# ESP-01_daughter_board.net
KiCad netlist of a schematic drawn in EAGLE
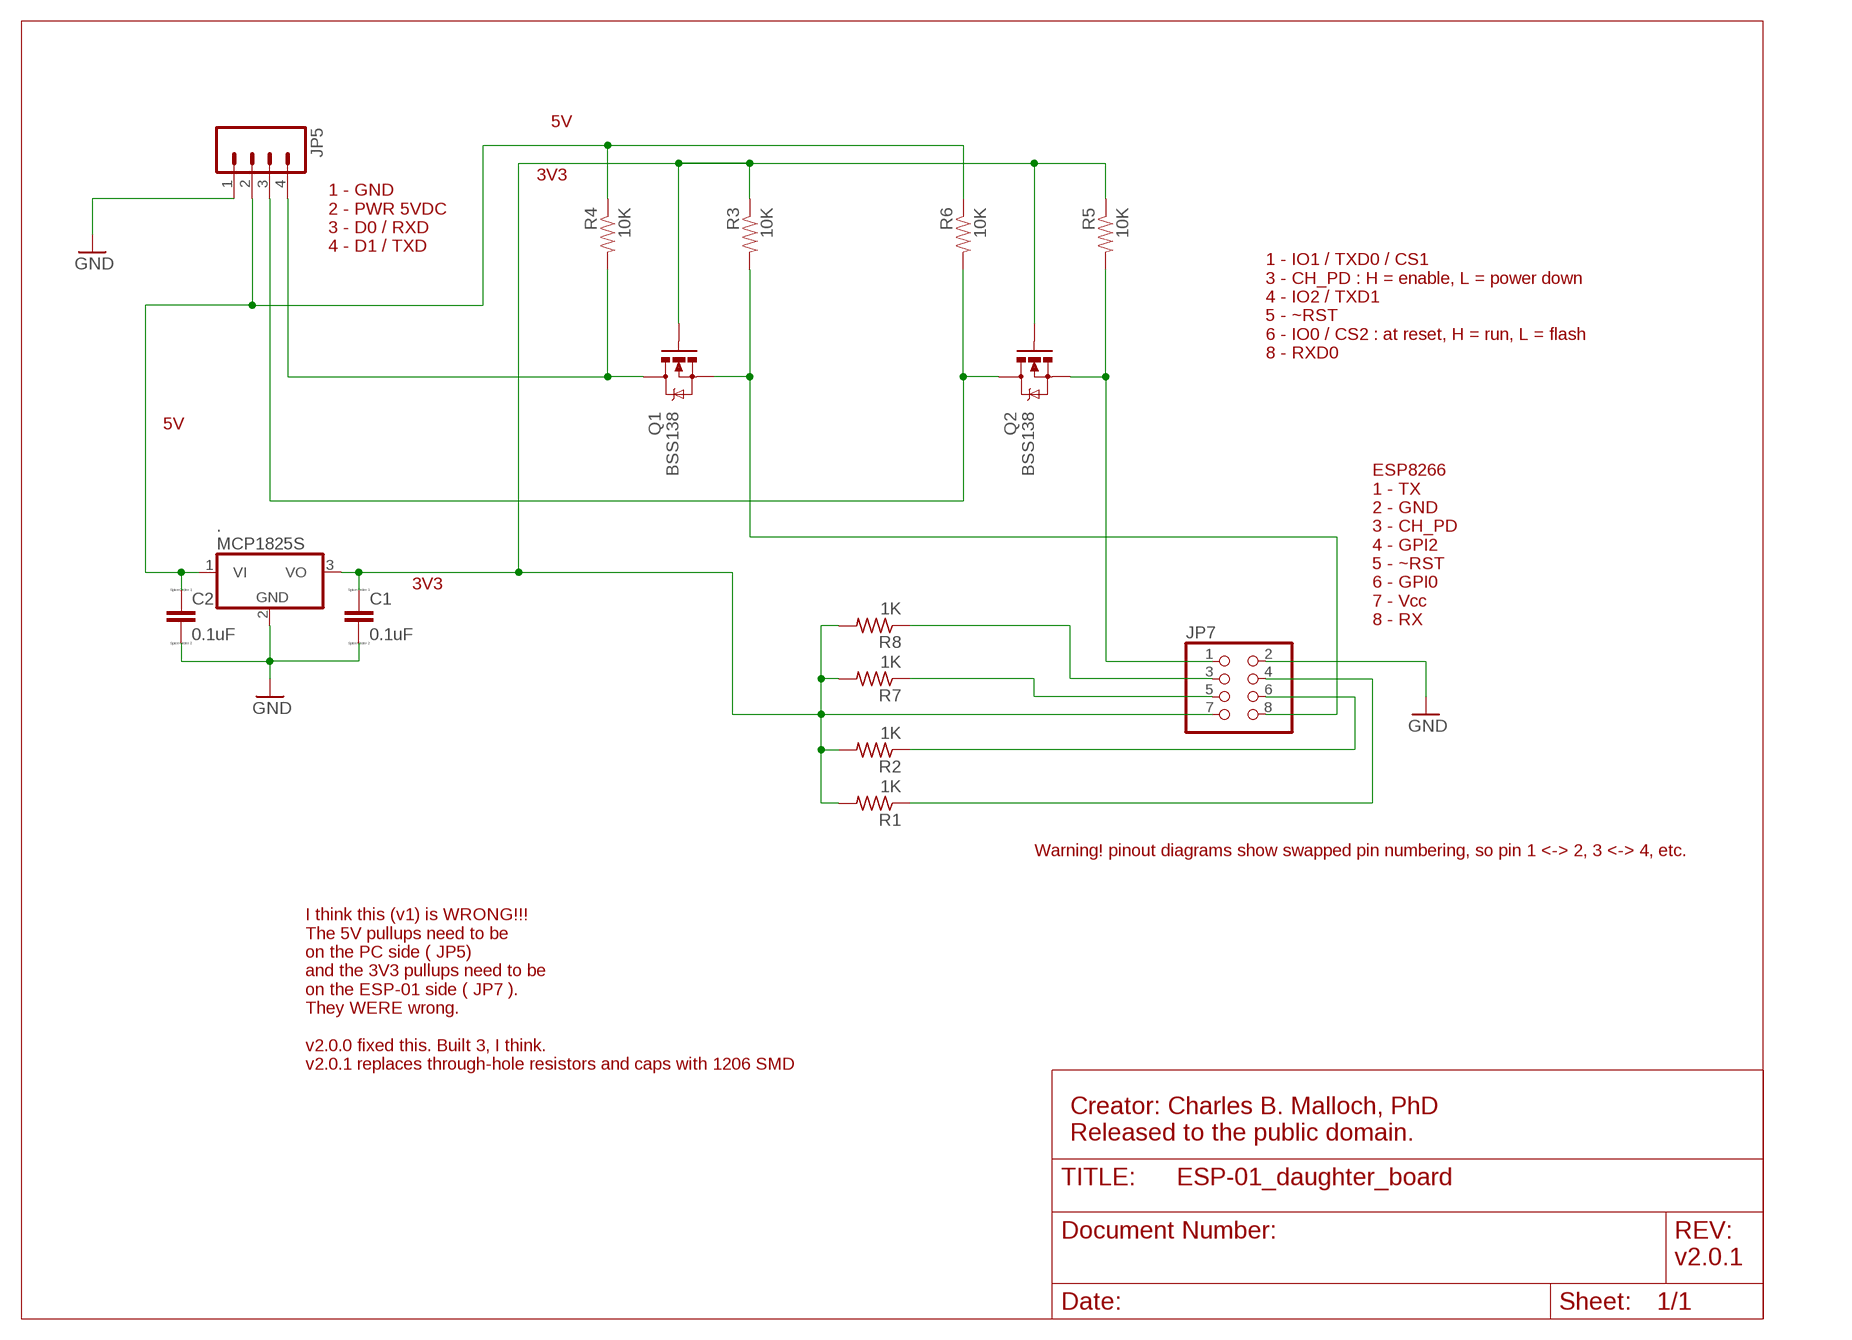
[diagram p0: schematic, sheet 1]

(export (version "E")
  (design (tool "Eeschema 10.0.6"))
  (components
    (comp (ref ".")
      (value "MCP1825S")
      (footprint "eagle-import:SOT223")
      (libsource (lib "eagle-import") (part "MCP1703DB"))
    )
    (comp (ref "C1")
      (value "0.1uF")
      (footprint "eagle-import:C1206")
      (libsource (lib "eagle-import") (part "CC1206"))
    )
    (comp (ref "C2")
      (value "0.1uF")
      (footprint "eagle-import:C1206")
      (libsource (lib "eagle-import") (part "CC1206"))
    )
    (comp (ref "JP5")
      (value "M04LOCK_LONGPADS")
      (footprint "eagle-import:1X04_LOCK_LONGPADS")
      (libsource (lib "eagle-import") (part "M04LOCK_LONGPADS"))
    )
    (comp (ref "JP7")
      (value "PINHD-2X4")
      (footprint "eagle-import:2X04")
      (libsource (lib "eagle-import") (part "PINHD-2X4"))
    )
    (comp (ref "Q1")
      (value "BSS138")
      (footprint "eagle-import:SOT23-3")
      (libsource (lib "eagle-import") (part "BSS138TRANS-00830"))
    )
    (comp (ref "Q2")
      (value "BSS138")
      (footprint "eagle-import:SOT23-3")
      (libsource (lib "eagle-import") (part "BSS138TRANS-00830"))
    )
    (comp (ref "R1")
      (value "1K")
      (footprint "eagle-import:M1206")
      (libsource (lib "eagle-import") (part "R-US_M1206"))
    )
    (comp (ref "R2")
      (value "1K")
      (footprint "eagle-import:M1206")
      (libsource (lib "eagle-import") (part "R-US_M1206"))
    )
    (comp (ref "R3")
      (value "10K")
      (footprint "eagle-import:1206")
      (libsource (lib "eagle-import") (part "RESISTOR1206"))
    )
    (comp (ref "R4")
      (value "10K")
      (footprint "eagle-import:1206")
      (libsource (lib "eagle-import") (part "RESISTOR1206"))
    )
    (comp (ref "R5")
      (value "10K")
      (footprint "eagle-import:1206")
      (libsource (lib "eagle-import") (part "RESISTOR1206"))
    )
    (comp (ref "R6")
      (value "10K")
      (footprint "eagle-import:1206")
      (libsource (lib "eagle-import") (part "RESISTOR1206"))
    )
    (comp (ref "R7")
      (value "1K")
      (footprint "eagle-import:M1206")
      (libsource (lib "eagle-import") (part "R-US_M1206"))
    )
    (comp (ref "R8")
      (value "1K")
      (footprint "eagle-import:M1206")
      (libsource (lib "eagle-import") (part "R-US_M1206"))
    )
  )
  (nets
    (net (code "1") (name "GND") (class "Default")
      (node (ref ".") (pin "2") (pinfunction "GND_2") (pintype "passive"))
      (node (ref "C1") (pin "2") (pinfunction "2_2") (pintype "passive"))
      (node (ref "C2") (pin "2") (pinfunction "2_2") (pintype "passive"))
      (node (ref "JP5") (pin "1") (pinfunction "1_1") (pintype "passive"))
      (node (ref "JP7") (pin "2") (pinfunction "2_2") (pintype "passive"))
    )
    (net (code "2") (name "Net-(.-VI)") (class "Default")
      (node (ref ".") (pin "1") (pinfunction "VI_1") (pintype "input"))
      (node (ref "C2") (pin "1") (pinfunction "1_1") (pintype "passive"))
      (node (ref "JP5") (pin "2") (pinfunction "2_2") (pintype "passive"))
      (node (ref "R4") (pin "1") (pinfunction "1_1") (pintype "passive"))
      (node (ref "R6") (pin "1") (pinfunction "1_1") (pintype "passive"))
    )
    (net (code "3") (name "Net-(.-VO)") (class "Default")
      (node (ref ".") (pin "3") (pinfunction "VO_3") (pintype "passive"))
      (node (ref "C1") (pin "1") (pinfunction "1_1") (pintype "passive"))
      (node (ref "JP7") (pin "7") (pinfunction "7_7") (pintype "passive"))
      (node (ref "Q1") (pin "1") (pinfunction "G_1") (pintype "passive"))
      (node (ref "Q2") (pin "1") (pinfunction "G_1") (pintype "passive"))
      (node (ref "R1") (pin "2") (pinfunction "2_2") (pintype "passive"))
      (node (ref "R2") (pin "2") (pinfunction "2_2") (pintype "passive"))
      (node (ref "R3") (pin "1") (pinfunction "1_1") (pintype "passive"))
      (node (ref "R5") (pin "1") (pinfunction "1_1") (pintype "passive"))
      (node (ref "R7") (pin "2") (pinfunction "2_2") (pintype "passive"))
      (node (ref "R8") (pin "2") (pinfunction "2_2") (pintype "passive"))
    )
    (net (code "4") (name "Net-(JP7-Pad3)") (class "Default")
      (node (ref "JP7") (pin "3") (pinfunction "3_3") (pintype "passive"))
      (node (ref "R8") (pin "1") (pinfunction "1_1") (pintype "passive"))
    )
    (net (code "5") (name "Net-(JP7-Pad4)") (class "Default")
      (node (ref "JP7") (pin "4") (pinfunction "4_4") (pintype "passive"))
      (node (ref "R1") (pin "1") (pinfunction "1_1") (pintype "passive"))
    )
    (net (code "6") (name "Net-(JP7-Pad5)") (class "Default")
      (node (ref "JP7") (pin "5") (pinfunction "5_5") (pintype "passive"))
      (node (ref "R7") (pin "1") (pinfunction "1_1") (pintype "passive"))
    )
    (net (code "7") (name "Net-(JP7-Pad6)") (class "Default")
      (node (ref "JP7") (pin "6") (pinfunction "6_6") (pintype "passive"))
      (node (ref "R2") (pin "1") (pinfunction "1_1") (pintype "passive"))
    )
    (net (code "8") (name "Net-(Q1-D)") (class "Default")
      (node (ref "JP5") (pin "4") (pinfunction "4_4") (pintype "passive"))
      (node (ref "Q1") (pin "3") (pinfunction "D_3") (pintype "passive"))
      (node (ref "R4") (pin "2") (pinfunction "2_2") (pintype "passive"))
    )
    (net (code "9") (name "Net-(Q1-S)") (class "Default")
      (node (ref "JP7") (pin "8") (pinfunction "8_8") (pintype "passive"))
      (node (ref "Q1") (pin "2") (pinfunction "S_2") (pintype "passive"))
      (node (ref "R3") (pin "2") (pinfunction "2_2") (pintype "passive"))
    )
    (net (code "10") (name "Net-(Q2-D)") (class "Default")
      (node (ref "JP5") (pin "3") (pinfunction "3_3") (pintype "passive"))
      (node (ref "Q2") (pin "3") (pinfunction "D_3") (pintype "passive"))
      (node (ref "R6") (pin "2") (pinfunction "2_2") (pintype "passive"))
    )
    (net (code "11") (name "Net-(Q2-S)") (class "Default")
      (node (ref "JP7") (pin "1") (pinfunction "1_1") (pintype "passive"))
      (node (ref "Q2") (pin "2") (pinfunction "S_2") (pintype "passive"))
      (node (ref "R5") (pin "2") (pinfunction "2_2") (pintype "passive"))
    )
  )
)
